# M_C_ext_main_ftdi.net
KiCad netlist of a schematic drawn in EAGLE
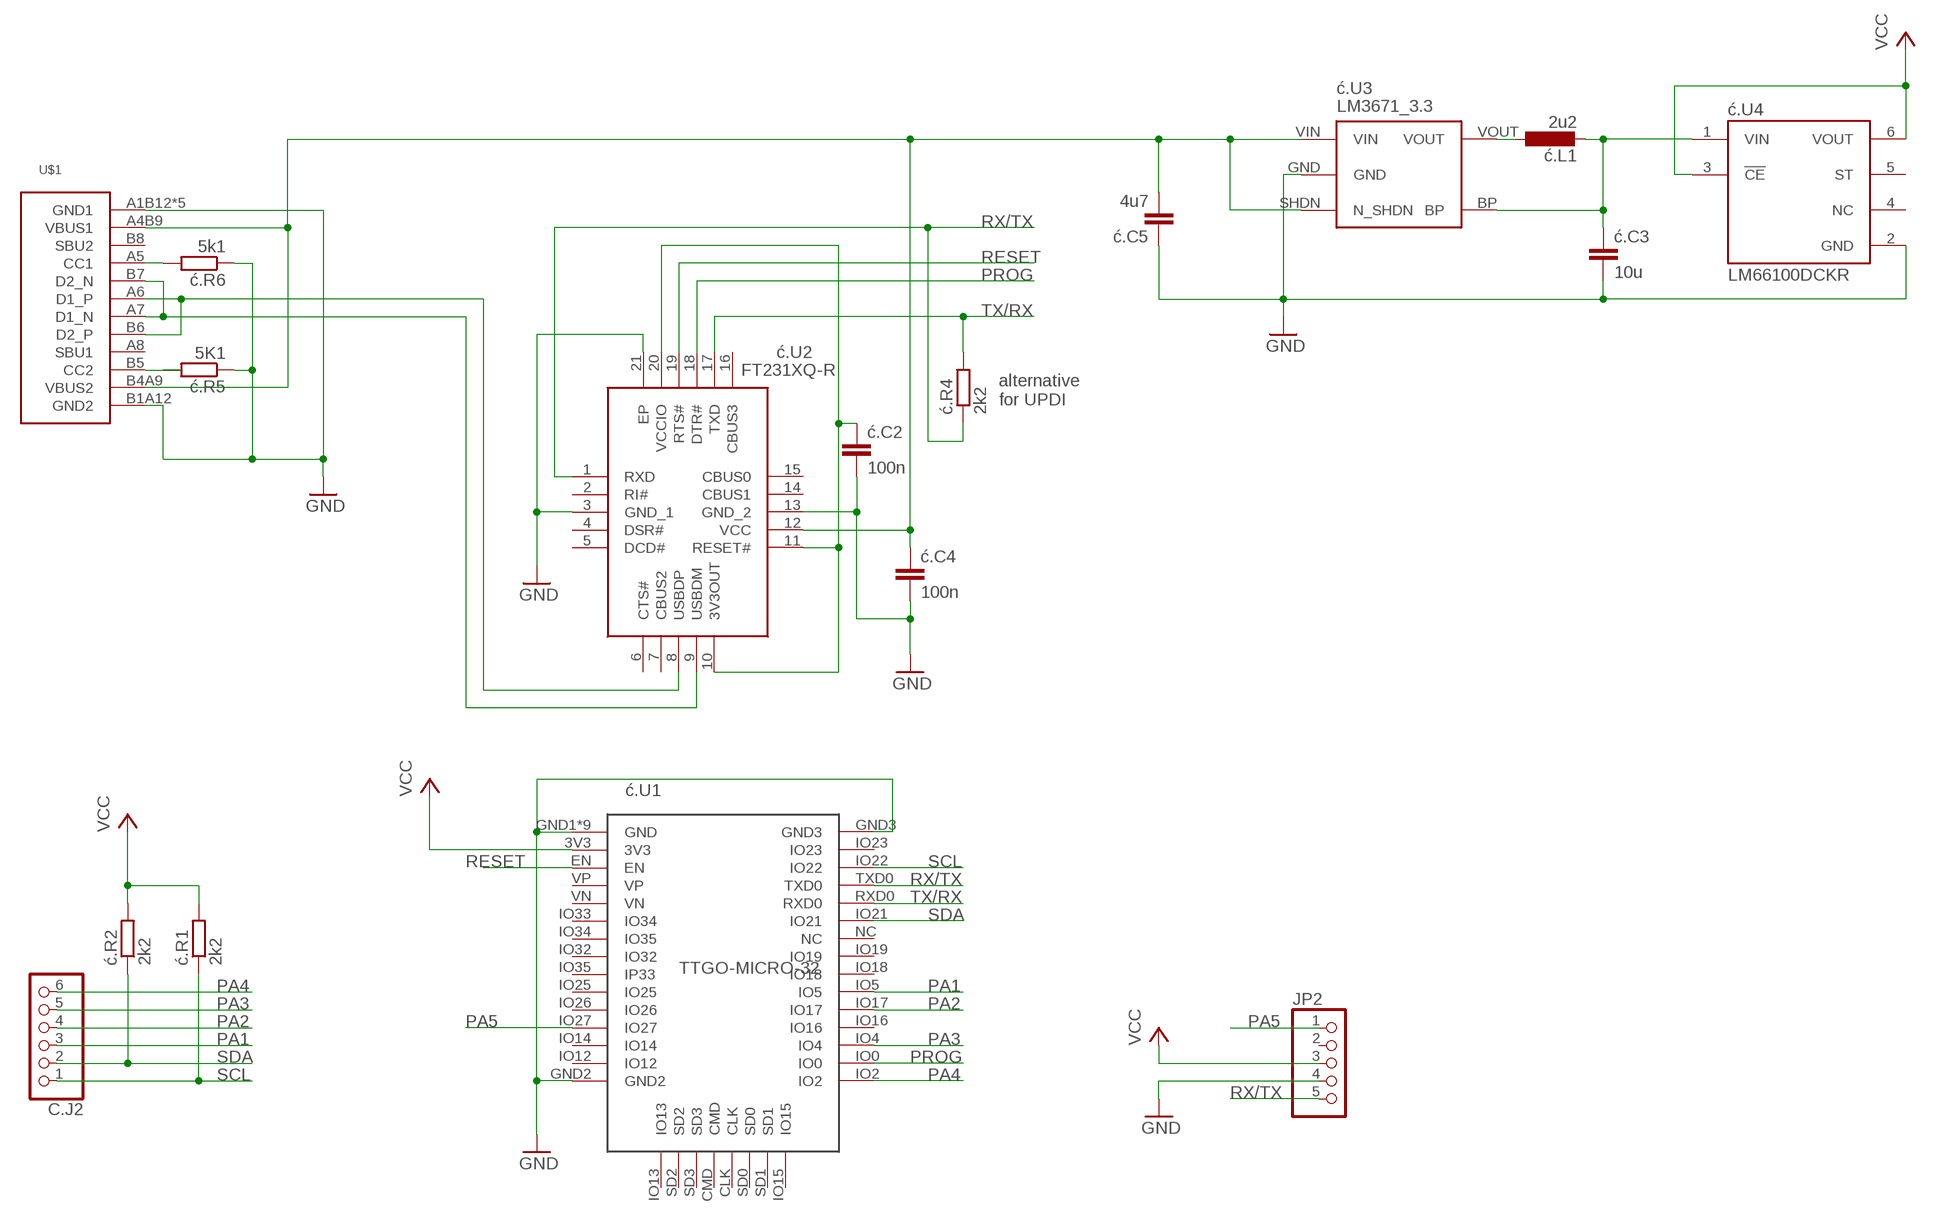
[diagram p0: schematic, sheet 1]

(export (version "E")
  (design (tool "Eeschema 10.0.6"))
  (components
    (comp (ref "C.J2")
      (value "PINHD-1X6")
      (footprint "eagle-import:1X06")
      (libsource (lib "eagle-import") (part "PINHD-1X6"))
    )
    (comp (ref "JP2")
      (value "PINHD-1X5")
      (footprint "eagle-import:1X05")
      (libsource (lib "eagle-import") (part "PINHD-1X5"))
    )
    (comp (ref "U$1")
      (value "USB-C")
      (footprint "eagle-import:USB-C")
      (libsource (lib "eagle-import") (part "USB-C"))
    )
    (comp (ref "ć.C2")
      (value "100n")
      (footprint "eagle-import:C0603")
      (libsource (lib "eagle-import") (part "C-EUC0603"))
    )
    (comp (ref "ć.C3")
      (value "10u")
      (footprint "eagle-import:C0603")
      (libsource (lib "eagle-import") (part "C-EUC0603"))
    )
    (comp (ref "ć.C4")
      (value "100n")
      (footprint "eagle-import:C0603")
      (libsource (lib "eagle-import") (part "C-EUC0603"))
    )
    (comp (ref "ć.C5")
      (value "4u7")
      (footprint "eagle-import:C0603")
      (libsource (lib "eagle-import") (part "C-EUC0603"))
    )
    (comp (ref "ć.L1")
      (value "2u2")
      (footprint "eagle-import:L3230M")
      (libsource (lib "eagle-import") (part "L-EUL3230M"))
    )
    (comp (ref "ć.R1")
      (value "2k2")
      (footprint "eagle-import:R0603")
      (libsource (lib "eagle-import") (part "R-EU_R0603"))
    )
    (comp (ref "ć.R2")
      (value "2k2")
      (footprint "eagle-import:R0603")
      (libsource (lib "eagle-import") (part "R-EU_R0603"))
    )
    (comp (ref "ć.R4")
      (value "2k2")
      (footprint "eagle-import:R0603")
      (libsource (lib "eagle-import") (part "R-EU_R0603"))
    )
    (comp (ref "ć.R5")
      (value "5K1")
      (footprint "eagle-import:R0603")
      (libsource (lib "eagle-import") (part "R-EU_R0603"))
    )
    (comp (ref "ć.R6")
      (value "5k1")
      (footprint "eagle-import:R0603")
      (libsource (lib "eagle-import") (part "R-EU_R0603"))
    )
    (comp (ref "ć.U1")
      (value "TTGO-MICRO-32")
      (footprint "eagle-import:TTGO-MICRO-32")
      (libsource (lib "eagle-import") (part "TTGO-MICRO-32"))
    )
    (comp (ref "ć.U2")
      (value "FT231XQ-R")
      (footprint "eagle-import:QFN50P400X400X80-21N")
      (libsource (lib "eagle-import") (part "FT231XQ-R"))
    )
    (comp (ref "ć.U3")
      (value "LM3671_3.3")
      (footprint "eagle-import:SOT32-5")
      (libsource (lib "eagle-import") (part "STABILISER_APE8865"))
    )
    (comp (ref "ć.U4")
      (value "LM66100DCKR")
      (footprint "eagle-import:SOT65P210X110-6N")
      (fields (field (name "MF") "Texas Instruments"))
      (libsource (lib "eagle-import") (part "LM66100DCKR"))
    )
  )
  (nets
    (net (code "1") (name "/PA1") (class "Default")
      (node (ref "C.J2") (pin "3") (pinfunction "3_3") (pintype "passive"))
      (node (ref "ć.U1") (pin "IO5") (pinfunction "IO5_IO5") (pintype "bidirectional"))
    )
    (net (code "2") (name "/PA2") (class "Default")
      (node (ref "C.J2") (pin "4") (pinfunction "4_4") (pintype "passive"))
      (node (ref "ć.U1") (pin "IO17") (pinfunction "IO17_IO17") (pintype "bidirectional"))
    )
    (net (code "3") (name "/PA3") (class "Default")
      (node (ref "C.J2") (pin "5") (pinfunction "5_5") (pintype "passive"))
      (node (ref "ć.U1") (pin "IO4") (pinfunction "IO4_IO4") (pintype "bidirectional"))
    )
    (net (code "4") (name "/PA4") (class "Default")
      (node (ref "C.J2") (pin "6") (pinfunction "6_6") (pintype "passive"))
      (node (ref "ć.U1") (pin "IO2") (pinfunction "IO2_IO2") (pintype "bidirectional"))
    )
    (net (code "5") (name "/PA5") (class "Default")
      (node (ref "JP2") (pin "1") (pinfunction "1_1") (pintype "passive"))
      (node (ref "ć.U1") (pin "IO27") (pinfunction "IO27_IO27") (pintype "bidirectional"))
    )
    (net (code "6") (name "/PROG") (class "Default")
      (node (ref "ć.U1") (pin "IO0") (pinfunction "IO0_IO0") (pintype "bidirectional"))
      (node (ref "ć.U2") (pin "18") (pinfunction "DTR#_18") (pintype "bidirectional"))
    )
    (net (code "7") (name "/RESET") (class "Default")
      (node (ref "ć.U1") (pin "EN") (pinfunction "EN_EN") (pintype "bidirectional"))
      (node (ref "ć.U2") (pin "19") (pinfunction "RTS#_19") (pintype "bidirectional"))
    )
    (net (code "8") (name "/RX{slash}TX") (class "Default")
      (node (ref "JP2") (pin "5") (pinfunction "5_5") (pintype "passive"))
      (node (ref "ć.R4") (pin "1") (pinfunction "1_1") (pintype "passive"))
      (node (ref "ć.U1") (pin "TXD0") (pinfunction "TXD0_TXD0") (pintype "bidirectional"))
      (node (ref "ć.U2") (pin "1") (pinfunction "RXD_1") (pintype "bidirectional"))
    )
    (net (code "9") (name "/SCL") (class "Default")
      (node (ref "C.J2") (pin "1") (pinfunction "1_1") (pintype "passive"))
      (node (ref "ć.R1") (pin "1") (pinfunction "1_1") (pintype "passive"))
      (node (ref "ć.U1") (pin "IO22") (pinfunction "IO22_IO22") (pintype "bidirectional"))
    )
    (net (code "10") (name "/SDA") (class "Default")
      (node (ref "C.J2") (pin "2") (pinfunction "2_2") (pintype "passive"))
      (node (ref "ć.R2") (pin "1") (pinfunction "1_1") (pintype "passive"))
      (node (ref "ć.U1") (pin "IO21") (pinfunction "IO21_IO21") (pintype "bidirectional"))
    )
    (net (code "11") (name "/TX{slash}RX") (class "Default")
      (node (ref "ć.R4") (pin "2") (pinfunction "2_2") (pintype "passive"))
      (node (ref "ć.U1") (pin "RXD0") (pinfunction "RXD0_RXD0") (pintype "bidirectional"))
      (node (ref "ć.U2") (pin "17") (pinfunction "TXD_17") (pintype "bidirectional"))
    )
    (net (code "12") (name "GND") (class "Default")
      (node (ref "JP2") (pin "4") (pinfunction "4_4") (pintype "passive"))
      (node (ref "U$1") (pin "A1B12") (pinfunction "GND1_A1B12") (pintype "bidirectional"))
      (node (ref "U$1") (pin "B1A12") (pinfunction "GND2_B1A12") (pintype "bidirectional"))
      (node (ref "U$1") (pin "SH1") (pinfunction "GND1_SH1") (pintype "bidirectional"))
      (node (ref "U$1") (pin "SH2") (pinfunction "GND1_SH2") (pintype "bidirectional"))
      (node (ref "U$1") (pin "SH3") (pinfunction "GND1_SH3") (pintype "bidirectional"))
      (node (ref "U$1") (pin "SH4") (pinfunction "GND1_SH4") (pintype "bidirectional"))
      (node (ref "ć.C2") (pin "2") (pinfunction "2_2") (pintype "passive"))
      (node (ref "ć.C3") (pin "2") (pinfunction "2_2") (pintype "passive"))
      (node (ref "ć.C4") (pin "2") (pinfunction "2_2") (pintype "passive"))
      (node (ref "ć.C5") (pin "1") (pinfunction "1_1") (pintype "passive"))
      (node (ref "ć.R5") (pin "1") (pinfunction "1_1") (pintype "passive"))
      (node (ref "ć.R6") (pin "1") (pinfunction "1_1") (pintype "passive"))
      (node (ref "ć.U1") (pin "GND1") (pinfunction "GND_GND1") (pintype "power_in"))
      (node (ref "ć.U1") (pin "GND10") (pinfunction "GND_GND10") (pintype "power_in"))
      (node (ref "ć.U1") (pin "GND11") (pinfunction "GND_GND11") (pintype "power_in"))
      (node (ref "ć.U1") (pin "GND2") (pinfunction "GND2_GND2") (pintype "power_in"))
      (node (ref "ć.U1") (pin "GND3") (pinfunction "GND3_GND3") (pintype "power_in"))
      (node (ref "ć.U1") (pin "GND4") (pinfunction "GND_GND4") (pintype "power_in"))
      (node (ref "ć.U1") (pin "GND5") (pinfunction "GND_GND5") (pintype "power_in"))
      (node (ref "ć.U1") (pin "GND6") (pinfunction "GND_GND6") (pintype "power_in"))
      (node (ref "ć.U1") (pin "GND7") (pinfunction "GND_GND7") (pintype "power_in"))
      (node (ref "ć.U1") (pin "GND8") (pinfunction "GND_GND8") (pintype "power_in"))
      (node (ref "ć.U1") (pin "GND9") (pinfunction "GND_GND9") (pintype "power_in"))
      (node (ref "ć.U2") (pin "13") (pinfunction "GND_2_13") (pintype "bidirectional"))
      (node (ref "ć.U2") (pin "21") (pinfunction "EP_21") (pintype "bidirectional"))
      (node (ref "ć.U2") (pin "3") (pinfunction "GND_1_3") (pintype "bidirectional"))
      (node (ref "ć.U3") (pin "GND") (pinfunction "GND_GND") (pintype "bidirectional"))
      (node (ref "ć.U4") (pin "2") (pinfunction "GND_2") (pintype "power_in"))
    )
    (net (code "13") (name "Net-(U$1-CC1)") (class "Default")
      (node (ref "U$1") (pin "A5") (pinfunction "CC1_A5") (pintype "bidirectional"))
      (node (ref "ć.R6") (pin "2") (pinfunction "2_2") (pintype "passive"))
    )
    (net (code "14") (name "Net-(U$1-CC2)") (class "Default")
      (node (ref "U$1") (pin "B5") (pinfunction "CC2_B5") (pintype "bidirectional"))
      (node (ref "ć.R5") (pin "2") (pinfunction "2_2") (pintype "passive"))
    )
    (net (code "15") (name "Net-(U$1-D1_N)") (class "Default")
      (node (ref "U$1") (pin "A7") (pinfunction "D1_N_A7") (pintype "bidirectional"))
      (node (ref "U$1") (pin "B7") (pinfunction "D2_N_B7") (pintype "bidirectional"))
      (node (ref "ć.U2") (pin "9") (pinfunction "USBDM_9") (pintype "bidirectional"))
    )
    (net (code "16") (name "Net-(U$1-D1_P)") (class "Default")
      (node (ref "U$1") (pin "A6") (pinfunction "D1_P_A6") (pintype "bidirectional"))
      (node (ref "U$1") (pin "B6") (pinfunction "D2_P_B6") (pintype "bidirectional"))
      (node (ref "ć.U2") (pin "8") (pinfunction "USBDP_8") (pintype "bidirectional"))
    )
    (net (code "17") (name "Net-(U$1-VBUS1)") (class "Default")
      (node (ref "U$1") (pin "A4B9") (pinfunction "VBUS1_A4B9") (pintype "bidirectional"))
      (node (ref "U$1") (pin "B4A9") (pinfunction "VBUS2_B4A9") (pintype "bidirectional"))
      (node (ref "ć.C4") (pin "1") (pinfunction "1_1") (pintype "passive"))
      (node (ref "ć.C5") (pin "2") (pinfunction "2_2") (pintype "passive"))
      (node (ref "ć.U2") (pin "12") (pinfunction "VCC_12") (pintype "bidirectional"))
      (node (ref "ć.U3") (pin "SHDN") (pinfunction "N_SHDN_SHDN") (pintype "bidirectional"))
      (node (ref "ć.U3") (pin "VIN") (pinfunction "VIN_VIN") (pintype "bidirectional"))
    )
    (net (code "18") (name "Net-(ć.L1-Pad1)") (class "Default")
      (node (ref "ć.L1") (pin "1") (pinfunction "1_1") (pintype "passive"))
      (node (ref "ć.U3") (pin "VOUT") (pinfunction "VOUT_VOUT") (pintype "bidirectional"))
    )
    (net (code "19") (name "Net-(ć.U2-3V3OUT)") (class "Default")
      (node (ref "ć.C2") (pin "1") (pinfunction "1_1") (pintype "passive"))
      (node (ref "ć.U2") (pin "10") (pinfunction "3V3OUT_10") (pintype "bidirectional"))
      (node (ref "ć.U2") (pin "11") (pinfunction "RESET#_11") (pintype "bidirectional"))
      (node (ref "ć.U2") (pin "20") (pinfunction "VCCIO_20") (pintype "bidirectional"))
    )
    (net (code "20") (name "Net-(ć.U4-VIN)") (class "Default")
      (node (ref "ć.C3") (pin "1") (pinfunction "1_1") (pintype "passive"))
      (node (ref "ć.L1") (pin "2") (pinfunction "2_2") (pintype "passive"))
      (node (ref "ć.U3") (pin "BP") (pinfunction "BP_BP") (pintype "bidirectional"))
      (node (ref "ć.U4") (pin "1") (pinfunction "VIN_1") (pintype "input"))
    )
    (net (code "21") (name "VCC") (class "Default")
      (node (ref "JP2") (pin "3") (pinfunction "3_3") (pintype "passive"))
      (node (ref "ć.R1") (pin "2") (pinfunction "2_2") (pintype "passive"))
      (node (ref "ć.R2") (pin "2") (pinfunction "2_2") (pintype "passive"))
      (node (ref "ć.U1") (pin "3V3") (pinfunction "3V3_3V3") (pintype "power_in"))
      (node (ref "ć.U4") (pin "3") (pinfunction "~{CE}_3") (pintype "input"))
      (node (ref "ć.U4") (pin "6") (pinfunction "VOUT_6") (pintype "output"))
    )
    (net (code "22") (name "unconnected-(JP2-Pad2)") (class "Default")
      (node (ref "JP2") (pin "2") (pinfunction "2_2") (pintype "passive"))
    )
    (net (code "23") (name "unconnected-(U$1-SBU1-PadA8)") (class "Default")
      (node (ref "U$1") (pin "A8") (pinfunction "SBU1_A8") (pintype "bidirectional"))
    )
    (net (code "24") (name "unconnected-(U$1-SBU2-PadB8)") (class "Default")
      (node (ref "U$1") (pin "B8") (pinfunction "SBU2_B8") (pintype "bidirectional"))
    )
    (net (code "25") (name "unconnected-(ć.U1-IO34-PadIO33)") (class "Default")
      (node (ref "ć.U1") (pin "IO33") (pinfunction "IO34_IO33") (pintype "bidirectional"))
    )
    (net (code "26") (name "unconnected-(ć.U1-IO35-PadIO34)") (class "Default")
      (node (ref "ć.U1") (pin "IO34") (pinfunction "IO35_IO34") (pintype "bidirectional"))
    )
    (net (code "27") (name "unconnected-(ć.U1-IP33-PadIO35)") (class "Default")
      (node (ref "ć.U1") (pin "IO35") (pinfunction "IP33_IO35") (pintype "bidirectional"))
    )
    (net (code "28") (name "unconnected-(ć.U1-PadCLK)") (class "Default")
      (node (ref "ć.U1") (pin "CLK") (pinfunction "CLK_CLK") (pintype "bidirectional"))
    )
    (net (code "29") (name "unconnected-(ć.U1-PadCMD)") (class "Default")
      (node (ref "ć.U1") (pin "CMD") (pinfunction "CMD_CMD") (pintype "bidirectional"))
    )
    (net (code "30") (name "unconnected-(ć.U1-PadIO12)") (class "Default")
      (node (ref "ć.U1") (pin "IO12") (pinfunction "IO12_IO12") (pintype "bidirectional"))
    )
    (net (code "31") (name "unconnected-(ć.U1-PadIO13)") (class "Default")
      (node (ref "ć.U1") (pin "IO13") (pinfunction "IO13_IO13") (pintype "bidirectional"))
    )
    (net (code "32") (name "unconnected-(ć.U1-PadIO14)") (class "Default")
      (node (ref "ć.U1") (pin "IO14") (pinfunction "IO14_IO14") (pintype "bidirectional"))
    )
    (net (code "33") (name "unconnected-(ć.U1-PadIO15)") (class "Default")
      (node (ref "ć.U1") (pin "IO15") (pinfunction "IO15_IO15") (pintype "bidirectional"))
    )
    (net (code "34") (name "unconnected-(ć.U1-PadIO16)") (class "Default")
      (node (ref "ć.U1") (pin "IO16") (pinfunction "IO16_IO16") (pintype "bidirectional"))
    )
    (net (code "35") (name "unconnected-(ć.U1-PadIO18)") (class "Default")
      (node (ref "ć.U1") (pin "IO18") (pinfunction "IO18_IO18") (pintype "bidirectional"))
    )
    (net (code "36") (name "unconnected-(ć.U1-PadIO19)") (class "Default")
      (node (ref "ć.U1") (pin "IO19") (pinfunction "IO19_IO19") (pintype "bidirectional"))
    )
    (net (code "37") (name "unconnected-(ć.U1-PadIO23)") (class "Default")
      (node (ref "ć.U1") (pin "IO23") (pinfunction "IO23_IO23") (pintype "bidirectional"))
    )
    (net (code "38") (name "unconnected-(ć.U1-PadIO25)") (class "Default")
      (node (ref "ć.U1") (pin "IO25") (pinfunction "IO25_IO25") (pintype "bidirectional"))
    )
    (net (code "39") (name "unconnected-(ć.U1-PadIO26)") (class "Default")
      (node (ref "ć.U1") (pin "IO26") (pinfunction "IO26_IO26") (pintype "bidirectional"))
    )
    (net (code "40") (name "unconnected-(ć.U1-PadIO32)") (class "Default")
      (node (ref "ć.U1") (pin "IO32") (pinfunction "IO32_IO32") (pintype "bidirectional"))
    )
    (net (code "41") (name "unconnected-(ć.U1-PadNC)") (class "Default")
      (node (ref "ć.U1") (pin "NC") (pinfunction "NC_NC") (pintype "no_connect"))
    )
    (net (code "42") (name "unconnected-(ć.U1-PadSD0)") (class "Default")
      (node (ref "ć.U1") (pin "SD0") (pinfunction "SD0_SD0") (pintype "bidirectional"))
    )
    (net (code "43") (name "unconnected-(ć.U1-PadSD1)") (class "Default")
      (node (ref "ć.U1") (pin "SD1") (pinfunction "SD1_SD1") (pintype "bidirectional"))
    )
    (net (code "44") (name "unconnected-(ć.U1-PadSD2)") (class "Default")
      (node (ref "ć.U1") (pin "SD2") (pinfunction "SD2_SD2") (pintype "bidirectional"))
    )
    (net (code "45") (name "unconnected-(ć.U1-PadSD3)") (class "Default")
      (node (ref "ć.U1") (pin "SD3") (pinfunction "SD3_SD3") (pintype "bidirectional"))
    )
    (net (code "46") (name "unconnected-(ć.U1-PadVN)") (class "Default")
      (node (ref "ć.U1") (pin "VN") (pinfunction "VN_VN") (pintype "bidirectional"))
    )
    (net (code "47") (name "unconnected-(ć.U1-PadVP)") (class "Default")
      (node (ref "ć.U1") (pin "VP") (pinfunction "VP_VP") (pintype "bidirectional"))
    )
    (net (code "48") (name "unconnected-(ć.U2-CBUS0-Pad15)") (class "Default")
      (node (ref "ć.U2") (pin "15") (pinfunction "CBUS0_15") (pintype "bidirectional"))
    )
    (net (code "49") (name "unconnected-(ć.U2-CBUS1-Pad14)") (class "Default")
      (node (ref "ć.U2") (pin "14") (pinfunction "CBUS1_14") (pintype "bidirectional"))
    )
    (net (code "50") (name "unconnected-(ć.U2-CBUS2-Pad7)") (class "Default")
      (node (ref "ć.U2") (pin "7") (pinfunction "CBUS2_7") (pintype "bidirectional"))
    )
    (net (code "51") (name "unconnected-(ć.U2-CBUS3-Pad16)") (class "Default")
      (node (ref "ć.U2") (pin "16") (pinfunction "CBUS3_16") (pintype "bidirectional"))
    )
    (net (code "52") (name "unconnected-(ć.U2-CTS#-Pad6)") (class "Default")
      (node (ref "ć.U2") (pin "6") (pinfunction "CTS#_6") (pintype "bidirectional"))
    )
    (net (code "53") (name "unconnected-(ć.U2-DCD#-Pad5)") (class "Default")
      (node (ref "ć.U2") (pin "5") (pinfunction "DCD#_5") (pintype "bidirectional"))
    )
    (net (code "54") (name "unconnected-(ć.U2-DSR#-Pad4)") (class "Default")
      (node (ref "ć.U2") (pin "4") (pinfunction "DSR#_4") (pintype "bidirectional"))
    )
    (net (code "55") (name "unconnected-(ć.U2-RI#-Pad2)") (class "Default")
      (node (ref "ć.U2") (pin "2") (pinfunction "RI#_2") (pintype "bidirectional"))
    )
    (net (code "56") (name "unconnected-(ć.U4-NC-Pad4)") (class "Default")
      (node (ref "ć.U4") (pin "4") (pinfunction "NC_4") (pintype "no_connect"))
    )
    (net (code "57") (name "unconnected-(ć.U4-ST-Pad5)") (class "Default")
      (node (ref "ć.U4") (pin "5") (pinfunction "ST_5") (pintype "output"))
    )
  )
)
